# Un_SecUSB_2.net
KiCad netlist of a schematic drawn in EAGLE
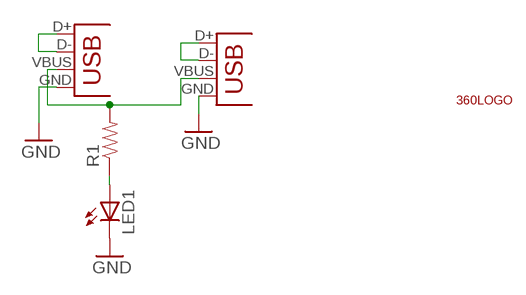
[diagram p0: schematic, sheet 1]

(export (version "E")
  (design (tool "Eeschema 10.0.6"))
  (components
    (comp (ref "LED1")
      (value "LED0603")
      (footprint "eagle-import:LED-0603")
      (libsource (lib "eagle-import") (part "LED0603"))
    )
    (comp (ref "R1")
      (value "RESISTOR0603-RES")
      (footprint "eagle-import:0603-RES")
      (libsource (lib "eagle-import") (part "RESISTOR0603-RES"))
    )
    (comp (ref "U$1")
      (value "360LOGO_0.8")
      (footprint "eagle-import:360LOGO_0.8")
      (libsource (lib "eagle-import") (part "360LOGO_0.8"))
    )
    (comp (ref "X2")
      (value "USB_4-A-H_2")
      (footprint "eagle-import:USB-A-H_2")
      (libsource (lib "eagle-import") (part "USB_4-A-H_2"))
    )
    (comp (ref "X3")
      (value "USB_4_3")
      (footprint "eagle-import:USB-A-3")
      (libsource (lib "eagle-import") (part "USB_4_3"))
    )
  )
  (nets
    (net (code "1") (name "GND") (class "Default")
      (node (ref "LED1") (pin "C") (pinfunction "C_C") (pintype "passive"))
      (node (ref "X2") (pin "GND") (pinfunction "GND_GND") (pintype "bidirectional"))
      (node (ref "X3") (pin "GND") (pinfunction "GND_GND") (pintype "bidirectional"))
    )
    (net (code "2") (name "Net-(LED1-PadA)") (class "Default")
      (node (ref "LED1") (pin "A") (pinfunction "A_A") (pintype "passive"))
      (node (ref "R1") (pin "1") (pinfunction "1_1") (pintype "passive"))
    )
    (net (code "3") (name "Net-(R1-Pad2)") (class "Default")
      (node (ref "R1") (pin "2") (pinfunction "2_2") (pintype "passive"))
      (node (ref "X2") (pin "VBUS") (pinfunction "VBUS_VBUS") (pintype "bidirectional"))
      (node (ref "X3") (pin "VBUS") (pinfunction "VBUS_VBUS") (pintype "bidirectional"))
    )
    (net (code "4") (name "Net-(X2-PadD+)") (class "Default")
      (node (ref "X2") (pin "D+") (pinfunction "D+_D+") (pintype "bidirectional"))
      (node (ref "X2") (pin "D-") (pinfunction "D-_D-") (pintype "bidirectional"))
    )
    (net (code "5") (name "Net-(X3-PadD+)") (class "Default")
      (node (ref "X3") (pin "D+") (pinfunction "D+_D+") (pintype "bidirectional"))
      (node (ref "X3") (pin "D-") (pinfunction "D-_D-") (pintype "bidirectional"))
    )
  )
)
